# 3_waffling60-DB_mcu.net
KiCad netlist of a schematic drawn in Altium Designer
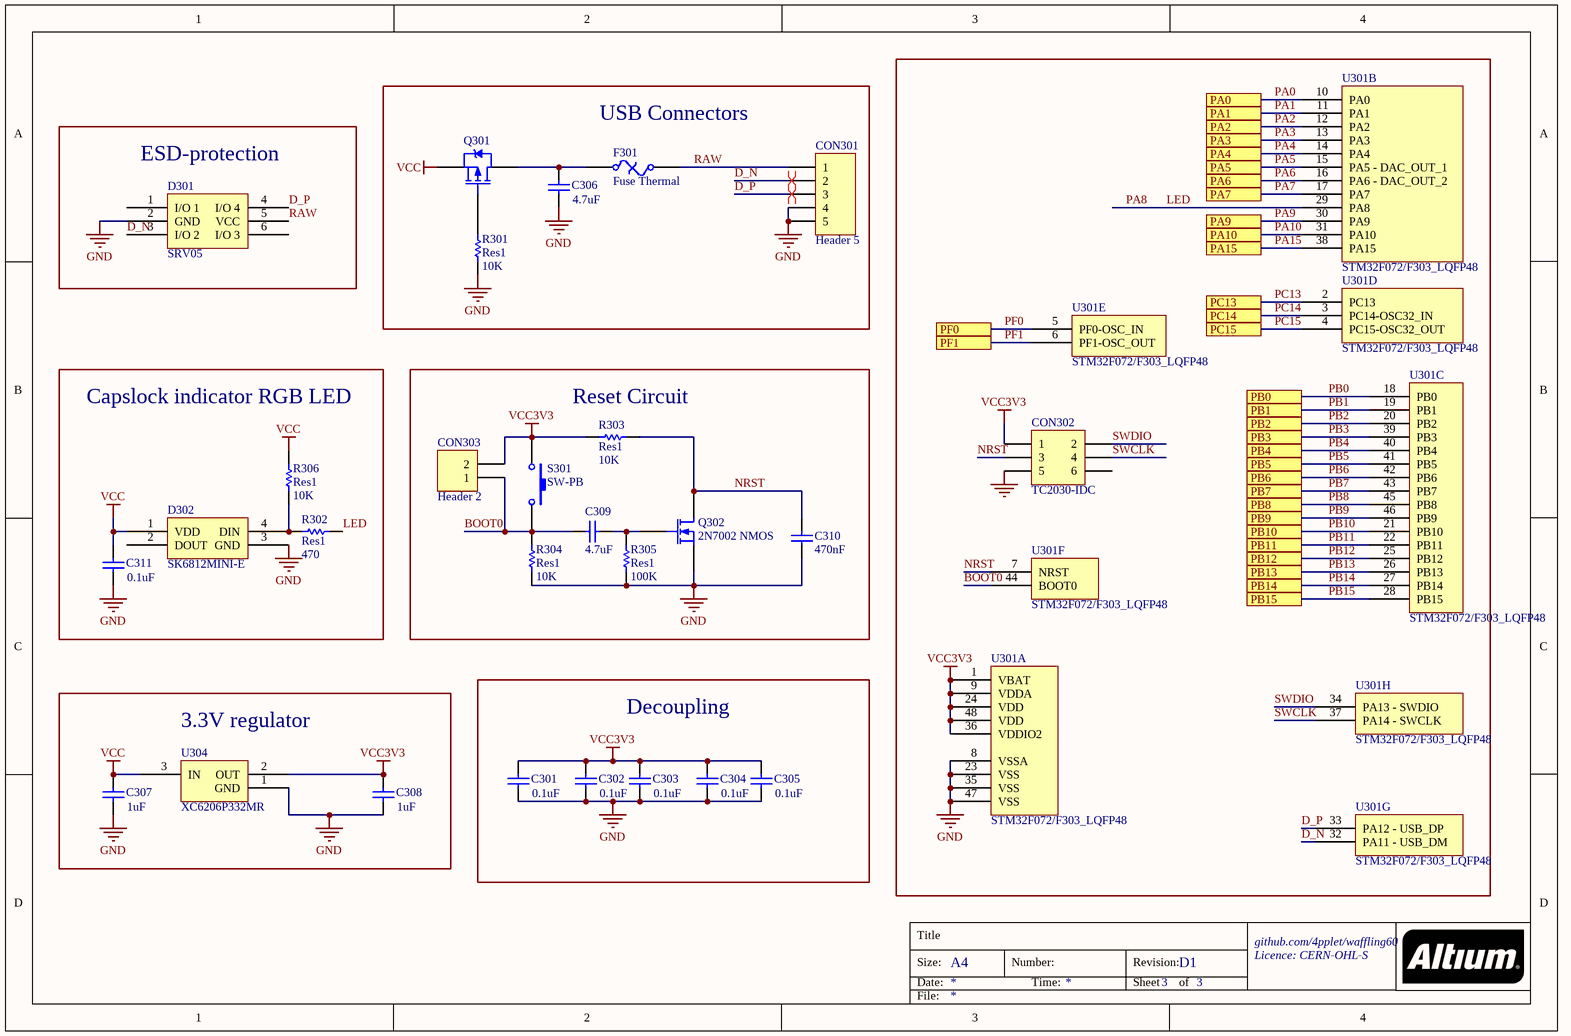
[diagram p0: 3_waffling60-DB_mcu.SchDoc]

(export (version "E")
  (design (tool "Eeschema 10.0.6"))
  (components
    (comp (ref "C301")
      (value "0.1uF")
      (footprint "C0603[1608]")
      (description "Capacitor")
      (fields (field (name "LCSC PART #") "C14663") (field (name "MRF.PART") "CC0603KRX7R9BB104"))
      (libsource (lib "Miscellaneous Devices") (part "Cap"))
    )
    (comp (ref "C302")
      (value "0.1uF")
      (footprint "C0603[1608]")
      (description "Capacitor")
      (fields (field (name "LCSC PART #") "C14663") (field (name "MRF.PART") "CC0603KRX7R9BB104"))
      (libsource (lib "Miscellaneous Devices") (part "Cap"))
    )
    (comp (ref "C303")
      (value "0.1uF")
      (footprint "C0603[1608]")
      (description "Capacitor")
      (fields (field (name "LCSC PART #") "C14663") (field (name "MRF.PART") "CC0603KRX7R9BB104"))
      (libsource (lib "Miscellaneous Devices") (part "Cap"))
    )
    (comp (ref "C304")
      (value "0.1uF")
      (footprint "C0603[1608]")
      (description "Capacitor")
      (fields (field (name "LCSC PART #") "C14663") (field (name "MRF.PART") "CC0603KRX7R9BB104"))
      (libsource (lib "Miscellaneous Devices") (part "Cap"))
    )
    (comp (ref "C305")
      (value "0.1uF")
      (footprint "C0603[1608]")
      (description "Capacitor")
      (fields (field (name "LCSC PART #") "C14663") (field (name "MRF.PART") "CC0603KRX7R9BB104"))
      (libsource (lib "Miscellaneous Devices") (part "Cap"))
    )
    (comp (ref "C306")
      (value "4.7uF")
      (footprint "C0603[1608]")
      (description "Capacitor")
      (fields (field (name "LCSC PART #") "C19666") (field (name "MRF.PART") "CL10A475KO8NNNC"))
      (libsource (lib "Miscellaneous Devices") (part "Cap"))
    )
    (comp (ref "C307")
      (value "1uF")
      (footprint "C0603[1608]")
      (description "Capacitor")
      (fields (field (name "LCSC PART #") "C15849") (field (name "MRF.PART") "CL10A105KB8NNNC"))
      (libsource (lib "Miscellaneous Devices") (part "Cap"))
    )
    (comp (ref "C308")
      (value "1uF")
      (footprint "C0603[1608]")
      (description "Capacitor")
      (fields (field (name "LCSC PART #") "C15849") (field (name "MRF.PART") "CL10A105KB8NNNC"))
      (libsource (lib "Miscellaneous Devices") (part "Cap"))
    )
    (comp (ref "C309")
      (value "4.7uF")
      (footprint "C0603[1608]")
      (description "Capacitor")
      (fields (field (name "LCSC PART #") "C19666") (field (name "MRF.PART") "CL10A475KO8NNNC"))
      (libsource (lib "Miscellaneous Devices") (part "Cap"))
    )
    (comp (ref "C310")
      (value "470nF")
      (footprint "C0603[1608]")
      (description "Capacitor")
      (fields (field (name "LCSC PART #") "C1623") (field (name "MRF.PART") "CL10B474KA8NNNC"))
      (libsource (lib "Miscellaneous Devices") (part "Cap"))
    )
    (comp (ref "C311")
      (value "0.1uF")
      (footprint "C0603[1608]")
      (description "Capacitor")
      (fields (field (name "LCSC PART #") "C14663") (field (name "MRF.PART") "CC0603KRX7R9BB104"))
      (libsource (lib "Miscellaneous Devices") (part "Cap"))
    )
    (comp (ref "CON301")
      (value "Header 5")
      (footprint "JST SM04B-SRSS-TB")
      (description "JST for USB daughter board")
      (fields (field (name "LCSC PART #") "C160404") (field (name "MRF.PART") "SM04B-SRSS-TB(LF)(SN)"))
      (libsource (lib "Miscellaneous Connectors") (part "Header 5"))
    )
    (comp (ref "CON302")
      (value "TC2030-IDC")
      (footprint "TC2030-IDC-NL")
      (description "Header, 3-Pin, Dual row")
      (libsource (lib "Miscellaneous Connectors") (part "Header 3X2"))
    )
    (comp (ref "CON303")
      (value "Header 2")
      (footprint "HDR1X2")
      (description "Header, 2-Pin")
      (libsource (lib "Miscellaneous Connectors") (part "Header 2"))
    )
    (comp (ref "D301")
      (value "SRV05")
      (footprint "SOT-23-6")
      (fields (field (name "LCSC PART #") "C85364") (field (name "MRF.PART") "SRV05-4-P-T7"))
      (libsource (lib "Keebs") (part "SRV05"))
    )
    (comp (ref "D302")
      (value "SK6812MINI-E")
      (footprint "SK6812MINI-E - shaped")
      (fields (field (name "LCSC PART #") "C524051") (field (name "MRF.PART") "DY-S352818/RGBC/6812-2T"))
      (libsource (lib "Keebs") (part "SK6812MINI-E"))
    )
    (comp (ref "F301")
      (value "Fuse Thermal")
      (footprint "C1206[3216]")
      (description "Thermal Fuse")
      (fields (field (name "LCSC PART #") "C135338") (field (name "MRF.PART") "ASMD1206-050"))
      (libsource (lib "Miscellaneous Devices") (part "Fuse Thermal"))
    )
    (comp (ref "Q301")
      (value "PMOS-2")
      (footprint "SOT-23-3")
      (description "P-Channel Power MOSFET")
      (fields (field (name "LCSC PART #") "C10487") (field (name "MRF.PART") "SI2301CDS-T1-GE3"))
      (libsource (lib "Miscellaneous Devices") (part "PMOS-2"))
    )
    (comp (ref "Q302")
      (value "2N7002 NMOS")
      (footprint "SOT-23-3")
      (description "N-Channel MOSFET")
      (fields (field (name "LCSC PART #") "C8545") (field (name "MRF.PART") "2N7002"))
      (libsource (lib "Miscellaneous Devices") (part "MOSFET-N"))
    )
    (comp (ref "R301")
      (value "Res1")
      (footprint "R0603[1608]")
      (description "Resistor")
      (fields
        (field (name "ALTIUM_VALUE") "10K")
        (field (name "LCSC PART #") "C25804")
        (field (name "MRF.PART") "0603WAF1002T5E")
      )
      (libsource (lib "Miscellaneous Devices") (part "Res1"))
    )
    (comp (ref "R302")
      (value "Res1")
      (footprint "R0603[1608]")
      (description "Resistor")
      (fields
        (field (name "ALTIUM_VALUE") "470")
        (field (name "LCSC PART #") "C23179")
        (field (name "MRF.PART") "0603WAF4700T5E")
      )
      (libsource (lib "Miscellaneous Devices") (part "Res1"))
    )
    (comp (ref "R303")
      (value "Res1")
      (footprint "R0603[1608]")
      (description "Resistor")
      (fields
        (field (name "ALTIUM_VALUE") "10K")
        (field (name "LCSC PART #") "C25804")
        (field (name "MRF.PART") "0603WAF1002T5E")
      )
      (libsource (lib "Miscellaneous Devices") (part "Res1"))
    )
    (comp (ref "R304")
      (value "Res1")
      (footprint "R0603[1608]")
      (description "Resistor")
      (fields
        (field (name "ALTIUM_VALUE") "10K")
        (field (name "LCSC PART #") "C25804")
        (field (name "MRF.PART") "0603WAF1002T5E")
      )
      (libsource (lib "Miscellaneous Devices") (part "Res1"))
    )
    (comp (ref "R305")
      (value "Res1")
      (footprint "R0603[1608]")
      (description "Resistor")
      (fields
        (field (name "ALTIUM_VALUE") "100K")
        (field (name "LCSC PART #") "C25803")
        (field (name "MRF.PART") "0603WAF1003T5E")
      )
      (libsource (lib "Miscellaneous Devices") (part "Res1"))
    )
    (comp (ref "R306")
      (value "Res1")
      (footprint "R0603[1608]")
      (description "Resistor")
      (fields
        (field (name "ALTIUM_VALUE") "10K")
        (field (name "LCSC PART #") "C25804")
        (field (name "MRF.PART") "0603WAF1002T5E")
      )
      (libsource (lib "Miscellaneous Devices") (part "Res1"))
    )
    (comp (ref "S301")
      (value "SW-PB")
      (footprint "XKB Switch")
      (description "Switch")
      (fields (field (name "MRF.PART") "TS-1187A-C-D-B") (field (name "LCSC PART #") "C318888"))
      (libsource (lib "Miscellaneous Devices") (part "SW-PB"))
    )
    (comp (ref "U301")
      (value "STM32F072/F303_LQFP48")
      (footprint "STM32 - COMBO 7X7MM")
      (fields (field (name "LCSC PART #") "C915660") (field (name "MRF.PART") "APM32F072CBT6"))
      (libsource (lib "Keebs") (part "STM32F072/F303_LQFP48"))
    )
    (comp (ref "U304")
      (value "XC6206P332MR")
      (footprint "SOT-23-3")
      (fields (field (name "LCSC PART #") "C5446"))
      (libsource (lib "Keebs") (part "SOT23 LDO"))
    )
  )
  (nets
    (net (code "1") (name "/BOOT0") (class "Default")
      (node (ref "C309") (pin "1") (pinfunction "1_1") (pintype "passive"))
      (node (ref "CON303") (pin "1") (pinfunction "1_1") (pintype "passive"))
      (node (ref "R304") (pin "1") (pinfunction "1_1") (pintype "passive"))
      (node (ref "S301") (pin "2") (pinfunction "2_2") (pintype "passive"))
      (node (ref "U301") (pin "44") (pinfunction "BOOT0_44") (pintype "passive"))
    )
    (net (code "2") (name "/D_N") (class "Default")
      (node (ref "CON301") (pin "2") (pinfunction "2_2") (pintype "passive"))
      (node (ref "D301") (pin "3") (pinfunction "I/O_2_3") (pintype "passive"))
      (node (ref "U301") (pin "32") (pinfunction "PA11_-_USB_DM_32") (pintype "passive"))
    )
    (net (code "3") (name "/D_P") (class "Default")
      (node (ref "CON301") (pin "3") (pinfunction "3_3") (pintype "passive"))
      (node (ref "D301") (pin "4") (pinfunction "I/O_4_4") (pintype "passive"))
      (node (ref "U301") (pin "33") (pinfunction "PA12_-_USB_DP_33") (pintype "passive"))
    )
    (net (code "4") (name "/LED") (class "Default")
      (node (ref "R302") (pin "2") (pinfunction "2_2") (pintype "passive"))
      (node (ref "U301") (pin "29") (pinfunction "PA8_29") (pintype "passive"))
    )
    (net (code "5") (name "/NRST") (class "Default")
      (node (ref "C310") (pin "1") (pinfunction "1_1") (pintype "passive"))
      (node (ref "CON302") (pin "3") (pinfunction "3_3") (pintype "passive"))
      (node (ref "Q302") (pin "3") (pinfunction "D_3") (pintype "passive"))
      (node (ref "R303") (pin "2") (pinfunction "2_2") (pintype "passive"))
      (node (ref "U301") (pin "7") (pinfunction "NRST_7") (pintype "passive"))
    )
    (net (code "6") (name "/PA0") (class "Default")
      (node (ref "U301") (pin "10") (pinfunction "PA0_10") (pintype "passive"))
    )
    (net (code "7") (name "/PA1") (class "Default")
      (node (ref "U301") (pin "11") (pinfunction "PA1_11") (pintype "passive"))
    )
    (net (code "8") (name "/PA2") (class "Default")
      (node (ref "U301") (pin "12") (pinfunction "PA2_12") (pintype "passive"))
    )
    (net (code "9") (name "/PA3") (class "Default")
      (node (ref "U301") (pin "13") (pinfunction "PA3_13") (pintype "passive"))
    )
    (net (code "10") (name "/PA4") (class "Default")
      (node (ref "U301") (pin "14") (pinfunction "PA4_14") (pintype "passive"))
    )
    (net (code "11") (name "/PA5") (class "Default")
      (node (ref "U301") (pin "15") (pinfunction "PA5_-_DAC_OUT_1_15") (pintype "passive"))
    )
    (net (code "12") (name "/PA6") (class "Default")
      (node (ref "U301") (pin "16") (pinfunction "PA6_-_DAC_OUT_2_16") (pintype "passive"))
    )
    (net (code "13") (name "/PA7") (class "Default")
      (node (ref "U301") (pin "17") (pinfunction "PA7_17") (pintype "passive"))
    )
    (net (code "14") (name "/PA9") (class "Default")
      (node (ref "U301") (pin "30") (pinfunction "PA9_30") (pintype "passive"))
    )
    (net (code "15") (name "/PA10") (class "Default")
      (node (ref "U301") (pin "31") (pinfunction "PA10_31") (pintype "passive"))
    )
    (net (code "16") (name "/PA15") (class "Default")
      (node (ref "U301") (pin "38") (pinfunction "PA15_38") (pintype "passive"))
    )
    (net (code "17") (name "/PB0") (class "Default")
      (node (ref "U301") (pin "18") (pinfunction "PB0_18") (pintype "passive"))
    )
    (net (code "18") (name "/PB1") (class "Default")
      (node (ref "U301") (pin "19") (pinfunction "PB1_19") (pintype "passive"))
    )
    (net (code "19") (name "/PB2") (class "Default")
      (node (ref "U301") (pin "20") (pinfunction "PB2_20") (pintype "passive"))
    )
    (net (code "20") (name "/PB3") (class "Default")
      (node (ref "U301") (pin "39") (pinfunction "PB3_39") (pintype "passive"))
    )
    (net (code "21") (name "/PB4") (class "Default")
      (node (ref "U301") (pin "40") (pinfunction "PB4_40") (pintype "passive"))
    )
    (net (code "22") (name "/PB5") (class "Default")
      (node (ref "U301") (pin "41") (pinfunction "PB5_41") (pintype "passive"))
    )
    (net (code "23") (name "/PB6") (class "Default")
      (node (ref "U301") (pin "42") (pinfunction "PB6_42") (pintype "passive"))
    )
    (net (code "24") (name "/PB7") (class "Default")
      (node (ref "U301") (pin "43") (pinfunction "PB7_43") (pintype "passive"))
    )
    (net (code "25") (name "/PB8") (class "Default")
      (node (ref "U301") (pin "45") (pinfunction "PB8_45") (pintype "passive"))
    )
    (net (code "26") (name "/PB9") (class "Default")
      (node (ref "U301") (pin "46") (pinfunction "PB9_46") (pintype "passive"))
    )
    (net (code "27") (name "/PB10") (class "Default")
      (node (ref "U301") (pin "21") (pinfunction "PB10_21") (pintype "passive"))
    )
    (net (code "28") (name "/PB11") (class "Default")
      (node (ref "U301") (pin "22") (pinfunction "PB11_22") (pintype "passive"))
    )
    (net (code "29") (name "/PB12") (class "Default")
      (node (ref "U301") (pin "25") (pinfunction "PB12_25") (pintype "passive"))
    )
    (net (code "30") (name "/PB13") (class "Default")
      (node (ref "U301") (pin "26") (pinfunction "PB13_26") (pintype "passive"))
    )
    (net (code "31") (name "/PB14") (class "Default")
      (node (ref "U301") (pin "27") (pinfunction "PB14_27") (pintype "passive"))
    )
    (net (code "32") (name "/PB15") (class "Default")
      (node (ref "U301") (pin "28") (pinfunction "PB15_28") (pintype "passive"))
    )
    (net (code "33") (name "/PC13") (class "Default")
      (node (ref "U301") (pin "2") (pinfunction "PC13_2") (pintype "passive"))
    )
    (net (code "34") (name "/PC14") (class "Default")
      (node (ref "U301") (pin "3") (pinfunction "PC14-OSC32_IN_3") (pintype "passive"))
    )
    (net (code "35") (name "/PC15") (class "Default")
      (node (ref "U301") (pin "4") (pinfunction "PC15-OSC32_OUT_4") (pintype "passive"))
    )
    (net (code "36") (name "/PF0") (class "Default")
      (node (ref "U301") (pin "5") (pinfunction "PF0-OSC_IN_5") (pintype "passive"))
    )
    (net (code "37") (name "/PF1") (class "Default")
      (node (ref "U301") (pin "6") (pinfunction "PF1-OSC_OUT_6") (pintype "passive"))
    )
    (net (code "38") (name "/RAW") (class "Default")
      (node (ref "CON301") (pin "1") (pinfunction "1_1") (pintype "passive"))
      (node (ref "D301") (pin "5") (pinfunction "VCC_5") (pintype "passive"))
      (node (ref "F301") (pin "2") (pinfunction "2_2") (pintype "passive"))
    )
    (net (code "39") (name "/SWCLK") (class "Default")
      (node (ref "CON302") (pin "4") (pinfunction "4_4") (pintype "passive"))
      (node (ref "U301") (pin "37") (pinfunction "PA14_-_SWCLK_37") (pintype "passive"))
    )
    (net (code "40") (name "/SWDIO") (class "Default")
      (node (ref "CON302") (pin "2") (pinfunction "2_2") (pintype "passive"))
      (node (ref "U301") (pin "34") (pinfunction "PA13_-_SWDIO_34") (pintype "passive"))
    )
    (net (code "41") (name "GND") (class "Default")
      (node (ref "C301") (pin "1") (pinfunction "1_1") (pintype "passive"))
      (node (ref "C302") (pin "1") (pinfunction "1_1") (pintype "passive"))
      (node (ref "C303") (pin "1") (pinfunction "1_1") (pintype "passive"))
      (node (ref "C304") (pin "1") (pinfunction "1_1") (pintype "passive"))
      (node (ref "C305") (pin "1") (pinfunction "1_1") (pintype "passive"))
      (node (ref "C306") (pin "1") (pinfunction "1_1") (pintype "passive"))
      (node (ref "C307") (pin "1") (pinfunction "1_1") (pintype "passive"))
      (node (ref "C308") (pin "1") (pinfunction "1_1") (pintype "passive"))
      (node (ref "C310") (pin "2") (pinfunction "2_2") (pintype "passive"))
      (node (ref "C311") (pin "1") (pinfunction "1_1") (pintype "passive"))
      (node (ref "CON301") (pin "4") (pinfunction "4_4") (pintype "passive"))
      (node (ref "CON301") (pin "5") (pinfunction "5_5") (pintype "passive"))
      (node (ref "CON302") (pin "5") (pinfunction "5_5") (pintype "passive"))
      (node (ref "D301") (pin "2") (pinfunction "GND_2") (pintype "passive"))
      (node (ref "D302") (pin "3") (pinfunction "GND_3") (pintype "passive"))
      (node (ref "Q302") (pin "2") (pinfunction "S_2") (pintype "passive"))
      (node (ref "R301") (pin "2") (pinfunction "2_2") (pintype "passive"))
      (node (ref "R304") (pin "2") (pinfunction "2_2") (pintype "passive"))
      (node (ref "R305") (pin "2") (pinfunction "2_2") (pintype "passive"))
      (node (ref "U301") (pin "23") (pinfunction "VSS_23") (pintype "passive"))
      (node (ref "U301") (pin "35") (pinfunction "VSS_35") (pintype "passive"))
      (node (ref "U301") (pin "47") (pinfunction "VSS_47") (pintype "passive"))
      (node (ref "U301") (pin "8") (pinfunction "VSSA_8") (pintype "passive"))
      (node (ref "U304") (pin "1") (pinfunction "GND_1") (pintype "passive"))
    )
    (net (code "42") (name "Net-(D302-DIN)") (class "Default")
      (node (ref "D302") (pin "4") (pinfunction "DIN_4") (pintype "passive"))
      (node (ref "R302") (pin "1") (pinfunction "1_1") (pintype "passive"))
      (node (ref "R306") (pin "2") (pinfunction "2_2") (pintype "passive"))
    )
    (net (code "43") (name "Net-(Q301-D)") (class "Default")
      (node (ref "C306") (pin "2") (pinfunction "2_2") (pintype "passive"))
      (node (ref "F301") (pin "1") (pinfunction "1_1") (pintype "passive"))
      (node (ref "Q301") (pin "3") (pinfunction "D_3") (pintype "passive"))
    )
    (net (code "44") (name "Net-(Q301-G)") (class "Default")
      (node (ref "Q301") (pin "1") (pinfunction "G_1") (pintype "passive"))
      (node (ref "R301") (pin "1") (pinfunction "1_1") (pintype "passive"))
    )
    (net (code "45") (name "Net-(Q302-G)") (class "Default")
      (node (ref "C309") (pin "2") (pinfunction "2_2") (pintype "passive"))
      (node (ref "Q302") (pin "1") (pinfunction "G_1") (pintype "passive"))
      (node (ref "R305") (pin "1") (pinfunction "1_1") (pintype "passive"))
    )
    (net (code "46") (name "VCC") (class "Default")
      (node (ref "C307") (pin "2") (pinfunction "2_2") (pintype "passive"))
      (node (ref "C311") (pin "2") (pinfunction "2_2") (pintype "passive"))
      (node (ref "D302") (pin "1") (pinfunction "VDD_1") (pintype "passive"))
      (node (ref "Q301") (pin "2") (pinfunction "S_2") (pintype "passive"))
      (node (ref "R306") (pin "1") (pinfunction "1_1") (pintype "passive"))
      (node (ref "U304") (pin "3") (pinfunction "IN_3") (pintype "passive"))
    )
    (net (code "47") (name "VCC3V3") (class "Default")
      (node (ref "C301") (pin "2") (pinfunction "2_2") (pintype "passive"))
      (node (ref "C302") (pin "2") (pinfunction "2_2") (pintype "passive"))
      (node (ref "C303") (pin "2") (pinfunction "2_2") (pintype "passive"))
      (node (ref "C304") (pin "2") (pinfunction "2_2") (pintype "passive"))
      (node (ref "C305") (pin "2") (pinfunction "2_2") (pintype "passive"))
      (node (ref "C308") (pin "2") (pinfunction "2_2") (pintype "passive"))
      (node (ref "CON302") (pin "1") (pinfunction "1_1") (pintype "passive"))
      (node (ref "CON303") (pin "2") (pinfunction "2_2") (pintype "passive"))
      (node (ref "R303") (pin "1") (pinfunction "1_1") (pintype "passive"))
      (node (ref "S301") (pin "1") (pinfunction "1_1") (pintype "passive"))
      (node (ref "U301") (pin "1") (pinfunction "VBAT_1") (pintype "passive"))
      (node (ref "U301") (pin "24") (pinfunction "VDD_24") (pintype "passive"))
      (node (ref "U301") (pin "36") (pinfunction "VDDIO2_36") (pintype "passive"))
      (node (ref "U301") (pin "48") (pinfunction "VDD_48") (pintype "passive"))
      (node (ref "U301") (pin "9") (pinfunction "VDDA_9") (pintype "passive"))
      (node (ref "U304") (pin "2") (pinfunction "OUT_2") (pintype "passive"))
    )
    (net (code "48") (name "unconnected-(CON302-Pad6)") (class "Default")
      (node (ref "CON302") (pin "6") (pinfunction "6_6") (pintype "passive"))
    )
    (net (code "49") (name "unconnected-(D301-I{slash}O_1-Pad1)") (class "Default")
      (node (ref "D301") (pin "1") (pinfunction "I/O_1_1") (pintype "passive"))
    )
    (net (code "50") (name "unconnected-(D301-I{slash}O_3-Pad6)") (class "Default")
      (node (ref "D301") (pin "6") (pinfunction "I/O_3_6") (pintype "passive"))
    )
    (net (code "51") (name "unconnected-(D302-DOUT-Pad2)") (class "Default")
      (node (ref "D302") (pin "2") (pinfunction "DOUT_2") (pintype "passive"))
    )
  )
)
